# MA-Ethernet.net
KiCad netlist of a schematic drawn in Altium Designer
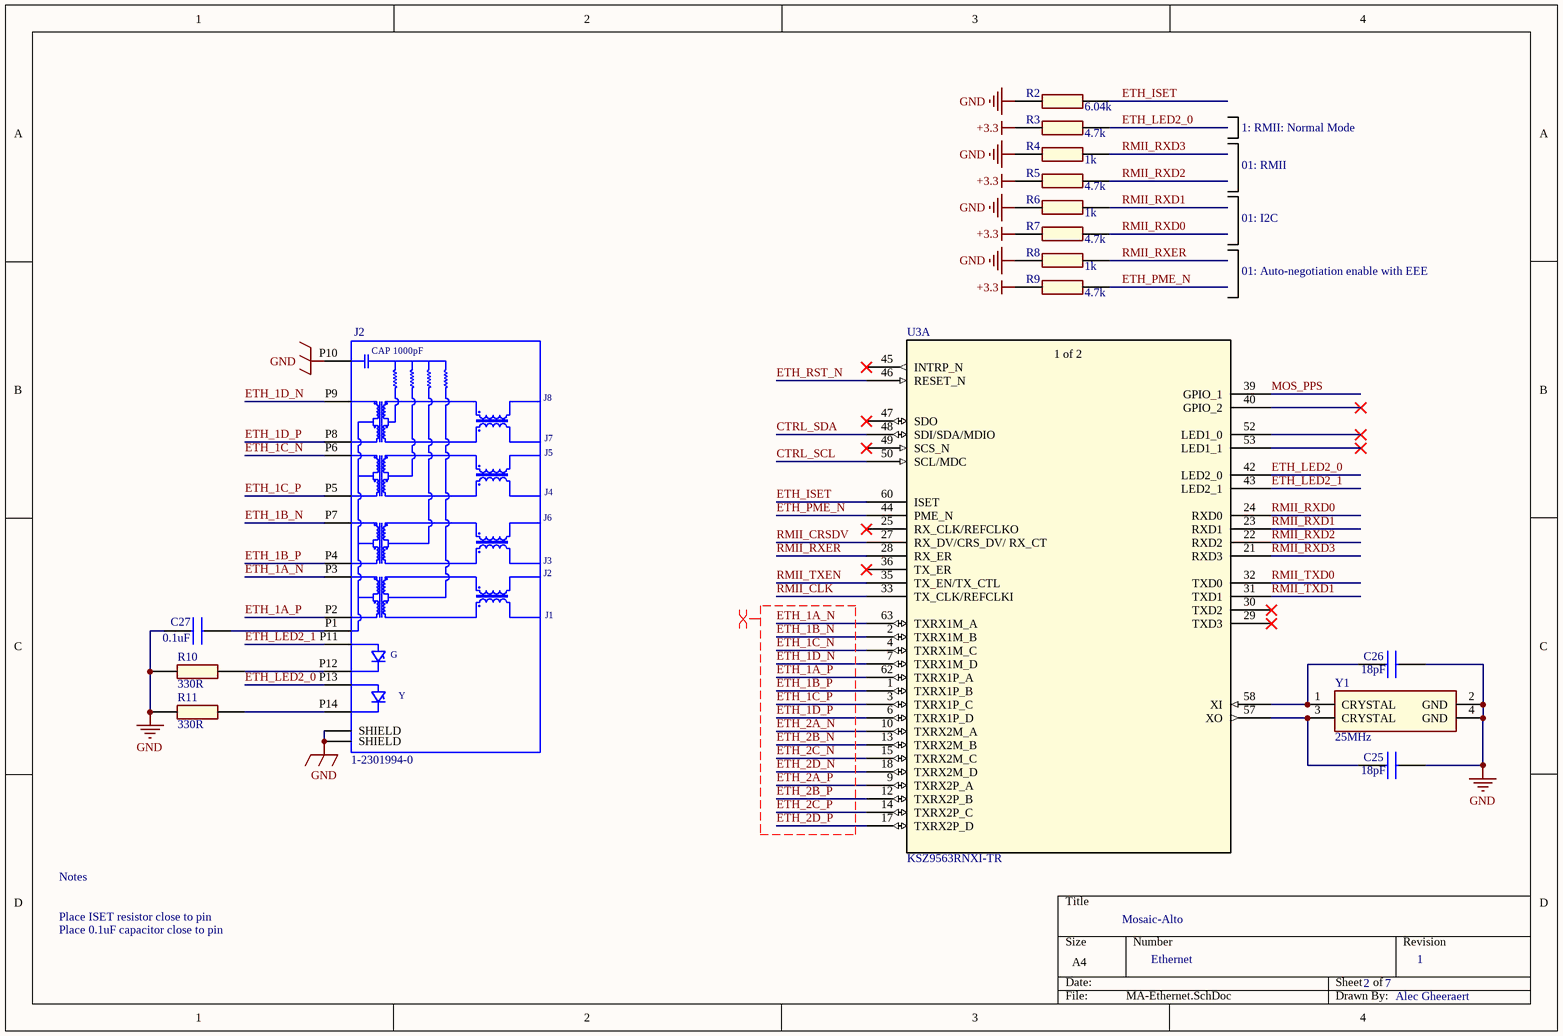
[diagram p0: MA-Ethernet.SchDoc]

(export (version "E")
  (design (tool "Eeschema 10.0.6"))
  (components
    (comp (ref "C25")
      (value "18pF")
      (footprint "CAPC1608X87N")
      (description "0603 18pF")
      (fields (field (name "TOLERANCE") "5%") (field (name "MANUFACTURER") "Walsin"))
      (libsource (lib "Ghrt") (part "0603N180J160CT"))
    )
    (comp (ref "C26")
      (value "18pF")
      (footprint "CAPC1608X87N")
      (description "0603 18pF")
      (fields (field (name "TOLERANCE") "5%") (field (name "MANUFACTURER") "Walsin"))
      (libsource (lib "Ghrt") (part "0603N180J160CT"))
    )
    (comp (ref "C27")
      (value "0.1uF")
      (footprint "CAPC2012X145N")
      (description "0805I 0.1µF")
      (fields (field (name "MANUFACTURER") "Walsin") (field (name "TOLERANCE") "10%"))
      (libsource (lib "Ghrt") (part "MG21B104K101CT"))
    )
    (comp (ref "J2")
      (value "1-2301994-0")
      (footprint "1-2301994-0")
      (description "RJ45 1Gbit MJ")
      (fields (field (name "MANUFACTURER") "TE Connectivity"))
      (libsource (lib "Ghrt") (part "1-2301994-0"))
    )
    (comp (ref "R2")
      (value "6.04k")
      (footprint "RESC1005X40N")
      (description "0402I 6.04k")
      (fields (field (name "MANUFACTURER") "Walsin") (field (name "TOLERANCE") "1%"))
      (libsource (lib "Ghrt") (part "WR04X6041FTL"))
    )
    (comp (ref "R3")
      (value "4.7k")
      (footprint "RESC1005X40N")
      (description "0402I 4.7k")
      (fields (field (name "MANUFACTURER") "Walsin") (field (name "TOLERANCE") "1%"))
      (libsource (lib "Ghrt") (part "WR04X4701FTL"))
    )
    (comp (ref "R4")
      (value "1k")
      (footprint "RESC1005X40N")
      (description "0402I 1k")
      (fields (field (name "MANUFACTURER") "Walsin") (field (name "TOLERANCE") "1%"))
      (libsource (lib "Ghrt") (part "WR04X1001FTL"))
    )
    (comp (ref "R5")
      (value "4.7k")
      (footprint "RESC1005X40N")
      (description "0402I 4.7k")
      (fields (field (name "MANUFACTURER") "Walsin") (field (name "TOLERANCE") "1%"))
      (libsource (lib "Ghrt") (part "WR04X4701FTL"))
    )
    (comp (ref "R6")
      (value "1k")
      (footprint "RESC1005X40N")
      (description "0402I 1k")
      (fields (field (name "MANUFACTURER") "Walsin") (field (name "TOLERANCE") "1%"))
      (libsource (lib "Ghrt") (part "WR04X1001FTL"))
    )
    (comp (ref "R7")
      (value "4.7k")
      (footprint "RESC1005X40N")
      (description "0402I 4.7k")
      (fields (field (name "MANUFACTURER") "Walsin") (field (name "TOLERANCE") "1%"))
      (libsource (lib "Ghrt") (part "WR04X4701FTL"))
    )
    (comp (ref "R8")
      (value "1k")
      (footprint "RESC1005X40N")
      (description "0402I 1k")
      (fields (field (name "MANUFACTURER") "Walsin") (field (name "TOLERANCE") "1%"))
      (libsource (lib "Ghrt") (part "WR04X1001FTL"))
    )
    (comp (ref "R9")
      (value "4.7k")
      (footprint "RESC1005X40N")
      (description "0402I 4.7k")
      (fields (field (name "MANUFACTURER") "Walsin") (field (name "TOLERANCE") "1%"))
      (libsource (lib "Ghrt") (part "WR04X4701FTL"))
    )
    (comp (ref "R10")
      (value "330R")
      (footprint "RESC1005X40N")
      (description "0402I 330")
      (fields (field (name "TOLERANCE") "1%") (field (name "MANUFACTURER") "Walsin"))
      (libsource (lib "Ghrt") (part "WR04X3300FTL"))
    )
    (comp (ref "R11")
      (value "330R")
      (footprint "RESC1005X40N")
      (description "0402I 330")
      (fields (field (name "TOLERANCE") "1%") (field (name "MANUFACTURER") "Walsin"))
      (libsource (lib "Ghrt") (part "WR04X3300FTL"))
    )
    (comp (ref "U3")
      (value "KSZ9563RNXI-TR")
      (footprint "VQFN64_NX_MCH")
      (description "3-Port Gigabit Ethernet Switch")
      (fields (field (name "MANUFACTURER") "Texas Instruments"))
      (libsource (lib "Ghrt") (part "KSZ9563RNXI-TR"))
    )
    (comp (ref "Y1")
      (value "25MHz")
      (footprint "LFXTAL055474REEL")
      (description "25MHz +/-50ppm Crystal")
      (fields (field (name "MANUFACTURER") "IQD") (field (name "TOLERANCE") "50PPM"))
      (libsource (lib "Ghrt") (part "LFXTAL055474REEL"))
    )
  )
  (nets
    (net (code "1") (name "+3.3") (class "Default")
      (node (ref "R3") (pin "1") (pinfunction "1_1") (pintype "passive"))
      (node (ref "R5") (pin "1") (pinfunction "1_1") (pintype "passive"))
      (node (ref "R7") (pin "1") (pinfunction "1_1") (pintype "passive"))
      (node (ref "R9") (pin "1") (pinfunction "1_1") (pintype "passive"))
    )
    (net (code "2") (name "/CTRL_SCL") (class "Default")
      (node (ref "U3") (pin "50") (pinfunction "SCL/MDC_50") (pintype "input"))
    )
    (net (code "3") (name "/CTRL_SDA") (class "Default")
      (node (ref "U3") (pin "48") (pinfunction "SDI/SDA/MDIO_48") (pintype "bidirectional"))
    )
    (net (code "4") (name "/ETH_1A_N") (class "Default")
      (node (ref "J2") (pin "P3") (pinfunction "P3_P3") (pintype "passive"))
      (node (ref "U3") (pin "63") (pinfunction "TXRX1M_A_63") (pintype "bidirectional"))
    )
    (net (code "5") (name "/ETH_1A_P") (class "Default")
      (node (ref "J2") (pin "P2") (pinfunction "P2_P2") (pintype "passive"))
      (node (ref "U3") (pin "62") (pinfunction "TXRX1P_A_62") (pintype "bidirectional"))
    )
    (net (code "6") (name "/ETH_1B_N") (class "Default")
      (node (ref "J2") (pin "P7") (pinfunction "P7_P7") (pintype "passive"))
      (node (ref "U3") (pin "2") (pinfunction "TXRX1M_B_2") (pintype "bidirectional"))
    )
    (net (code "7") (name "/ETH_1B_P") (class "Default")
      (node (ref "J2") (pin "P4") (pinfunction "P4_P4") (pintype "passive"))
      (node (ref "U3") (pin "1") (pinfunction "TXRX1P_B_1") (pintype "bidirectional"))
    )
    (net (code "8") (name "/ETH_1C_N") (class "Default")
      (node (ref "J2") (pin "P6") (pinfunction "P6_P6") (pintype "passive"))
      (node (ref "U3") (pin "4") (pinfunction "TXRX1M_C_4") (pintype "bidirectional"))
    )
    (net (code "9") (name "/ETH_1C_P") (class "Default")
      (node (ref "J2") (pin "P5") (pinfunction "P5_P5") (pintype "passive"))
      (node (ref "U3") (pin "3") (pinfunction "TXRX1P_C_3") (pintype "bidirectional"))
    )
    (net (code "10") (name "/ETH_1D_N") (class "Default")
      (node (ref "J2") (pin "P9") (pinfunction "P9_P9") (pintype "passive"))
      (node (ref "U3") (pin "7") (pinfunction "TXRX1M_D_7") (pintype "bidirectional"))
    )
    (net (code "11") (name "/ETH_1D_P") (class "Default")
      (node (ref "J2") (pin "P8") (pinfunction "P8_P8") (pintype "passive"))
      (node (ref "U3") (pin "6") (pinfunction "TXRX1P_D_6") (pintype "bidirectional"))
    )
    (net (code "12") (name "/ETH_2A_N") (class "Default")
      (node (ref "U3") (pin "10") (pinfunction "TXRX2M_A_10") (pintype "bidirectional"))
    )
    (net (code "13") (name "/ETH_2A_P") (class "Default")
      (node (ref "U3") (pin "9") (pinfunction "TXRX2P_A_9") (pintype "bidirectional"))
    )
    (net (code "14") (name "/ETH_2B_N") (class "Default")
      (node (ref "U3") (pin "13") (pinfunction "TXRX2M_B_13") (pintype "bidirectional"))
    )
    (net (code "15") (name "/ETH_2B_P") (class "Default")
      (node (ref "U3") (pin "12") (pinfunction "TXRX2P_B_12") (pintype "bidirectional"))
    )
    (net (code "16") (name "/ETH_2C_N") (class "Default")
      (node (ref "U3") (pin "15") (pinfunction "TXRX2M_C_15") (pintype "bidirectional"))
    )
    (net (code "17") (name "/ETH_2C_P") (class "Default")
      (node (ref "U3") (pin "14") (pinfunction "TXRX2P_C_14") (pintype "bidirectional"))
    )
    (net (code "18") (name "/ETH_2D_N") (class "Default")
      (node (ref "U3") (pin "18") (pinfunction "TXRX2M_D_18") (pintype "bidirectional"))
    )
    (net (code "19") (name "/ETH_2D_P") (class "Default")
      (node (ref "U3") (pin "17") (pinfunction "TXRX2P_D_17") (pintype "bidirectional"))
    )
    (net (code "20") (name "/ETH_ISET") (class "Default")
      (node (ref "R2") (pin "2") (pinfunction "2_2") (pintype "passive"))
      (node (ref "U3") (pin "60") (pinfunction "ISET_60") (pintype "passive"))
    )
    (net (code "21") (name "/ETH_LED2_0") (class "Default")
      (node (ref "J2") (pin "P13") (pinfunction "P13_P13") (pintype "passive"))
      (node (ref "R3") (pin "2") (pinfunction "2_2") (pintype "passive"))
      (node (ref "U3") (pin "42") (pinfunction "LED2_0_42") (pintype "passive"))
    )
    (net (code "22") (name "/ETH_LED2_1") (class "Default")
      (node (ref "J2") (pin "P11") (pinfunction "P11_P11") (pintype "passive"))
      (node (ref "U3") (pin "43") (pinfunction "LED2_1_43") (pintype "passive"))
    )
    (net (code "23") (name "/ETH_PME_N") (class "Default")
      (node (ref "R9") (pin "2") (pinfunction "2_2") (pintype "passive"))
      (node (ref "U3") (pin "44") (pinfunction "PME_N_44") (pintype "passive"))
    )
    (net (code "24") (name "/ETH_RST_N") (class "Default")
      (node (ref "U3") (pin "46") (pinfunction "RESET_N_46") (pintype "input"))
    )
    (net (code "25") (name "/MOS_PPS") (class "Default")
      (node (ref "U3") (pin "39") (pinfunction "GPIO_1_39") (pintype "passive"))
    )
    (net (code "26") (name "/RMII_CLK") (class "Default")
      (node (ref "U3") (pin "33") (pinfunction "TX_CLK/REFCLKI_33") (pintype "passive"))
    )
    (net (code "27") (name "/RMII_CRSDV") (class "Default")
      (node (ref "U3") (pin "27") (pinfunction "RX_DV/CRS_DV/_RX_CT_27") (pintype "passive"))
    )
    (net (code "28") (name "/RMII_RXD0") (class "Default")
      (node (ref "R7") (pin "2") (pinfunction "2_2") (pintype "passive"))
      (node (ref "U3") (pin "24") (pinfunction "RXD0_24") (pintype "passive"))
    )
    (net (code "29") (name "/RMII_RXD1") (class "Default")
      (node (ref "R6") (pin "2") (pinfunction "2_2") (pintype "passive"))
      (node (ref "U3") (pin "23") (pinfunction "RXD1_23") (pintype "passive"))
    )
    (net (code "30") (name "/RMII_RXD2") (class "Default")
      (node (ref "R5") (pin "2") (pinfunction "2_2") (pintype "passive"))
      (node (ref "U3") (pin "22") (pinfunction "RXD2_22") (pintype "passive"))
    )
    (net (code "31") (name "/RMII_RXD3") (class "Default")
      (node (ref "R4") (pin "2") (pinfunction "2_2") (pintype "passive"))
      (node (ref "U3") (pin "21") (pinfunction "RXD3_21") (pintype "passive"))
    )
    (net (code "32") (name "/RMII_RXER") (class "Default")
      (node (ref "R8") (pin "2") (pinfunction "2_2") (pintype "passive"))
      (node (ref "U3") (pin "28") (pinfunction "RX_ER_28") (pintype "passive"))
    )
    (net (code "33") (name "/RMII_TXD0") (class "Default")
      (node (ref "U3") (pin "32") (pinfunction "TXD0_32") (pintype "passive"))
    )
    (net (code "34") (name "/RMII_TXD1") (class "Default")
      (node (ref "U3") (pin "31") (pinfunction "TXD1_31") (pintype "passive"))
    )
    (net (code "35") (name "/RMII_TXEN") (class "Default")
      (node (ref "U3") (pin "35") (pinfunction "TX_EN/TX_CTL_35") (pintype "passive"))
    )
    (net (code "36") (name "GND") (class "Default")
      (node (ref "C25") (pin "2") (pinfunction "2_2") (pintype "passive"))
      (node (ref "C26") (pin "2") (pinfunction "2_2") (pintype "passive"))
      (node (ref "C27") (pin "2") (pinfunction "2_2") (pintype "passive"))
      (node (ref "J2") (pin "P10") (pinfunction "P10_P10") (pintype "passive"))
      (node (ref "J2") (pin "S1") (pinfunction "SHIELD_S1") (pintype "power_in"))
      (node (ref "J2") (pin "S2") (pinfunction "SHIELD_S2") (pintype "power_in"))
      (node (ref "R10") (pin "2") (pinfunction "2_2") (pintype "passive"))
      (node (ref "R11") (pin "2") (pinfunction "2_2") (pintype "passive"))
      (node (ref "R2") (pin "1") (pinfunction "1_1") (pintype "passive"))
      (node (ref "R4") (pin "1") (pinfunction "1_1") (pintype "passive"))
      (node (ref "R6") (pin "1") (pinfunction "1_1") (pintype "passive"))
      (node (ref "R8") (pin "1") (pinfunction "1_1") (pintype "passive"))
      (node (ref "Y1") (pin "2") (pinfunction "GND_2") (pintype "passive"))
      (node (ref "Y1") (pin "4") (pinfunction "GND_4") (pintype "passive"))
    )
    (net (code "37") (name "Net-(C27-Pad1)") (class "Default")
      (node (ref "C27") (pin "1") (pinfunction "1_1") (pintype "passive"))
      (node (ref "J2") (pin "P1") (pinfunction "P1_P1") (pintype "passive"))
    )
    (net (code "38") (name "Net-(J2-PadP12)") (class "Default")
      (node (ref "J2") (pin "P12") (pinfunction "P12_P12") (pintype "passive"))
      (node (ref "R10") (pin "1") (pinfunction "1_1") (pintype "passive"))
    )
    (net (code "39") (name "Net-(J2-PadP14)") (class "Default")
      (node (ref "J2") (pin "P14") (pinfunction "P14_P14") (pintype "passive"))
      (node (ref "R11") (pin "1") (pinfunction "1_1") (pintype "passive"))
    )
    (net (code "40") (name "Net-(U3A-XI)") (class "Default")
      (node (ref "C26") (pin "1") (pinfunction "1_1") (pintype "passive"))
      (node (ref "U3") (pin "58") (pinfunction "XI_58") (pintype "input"))
      (node (ref "Y1") (pin "1") (pinfunction "CRYSTAL_1") (pintype "passive"))
    )
    (net (code "41") (name "Net-(U3A-XO)") (class "Default")
      (node (ref "C25") (pin "1") (pinfunction "1_1") (pintype "passive"))
      (node (ref "U3") (pin "57") (pinfunction "XO_57") (pintype "output"))
      (node (ref "Y1") (pin "3") (pinfunction "CRYSTAL_3") (pintype "passive"))
    )
    (net (code "42") (name "unconnected-(U3A-GPIO_2-Pad40)") (class "Default")
      (node (ref "U3") (pin "40") (pinfunction "GPIO_2_40") (pintype "passive+no_connect"))
    )
    (net (code "43") (name "unconnected-(U3A-INTRP_N-Pad45)") (class "Default")
      (node (ref "U3") (pin "45") (pinfunction "INTRP_N_45") (pintype "output+no_connect"))
    )
    (net (code "44") (name "unconnected-(U3A-LED1_0-Pad52)") (class "Default")
      (node (ref "U3") (pin "52") (pinfunction "LED1_0_52") (pintype "passive+no_connect"))
    )
    (net (code "45") (name "unconnected-(U3A-LED1_1-Pad53)") (class "Default")
      (node (ref "U3") (pin "53") (pinfunction "LED1_1_53") (pintype "passive+no_connect"))
    )
    (net (code "46") (name "unconnected-(U3A-RX_CLK{slash}REFCLKO-Pad25)") (class "Default")
      (node (ref "U3") (pin "25") (pinfunction "RX_CLK/REFCLKO_25") (pintype "passive+no_connect"))
    )
    (net (code "47") (name "unconnected-(U3A-SCS_N-Pad49)") (class "Default")
      (node (ref "U3") (pin "49") (pinfunction "SCS_N_49") (pintype "input+no_connect"))
    )
    (net (code "48") (name "unconnected-(U3A-SDO-Pad47)") (class "Default")
      (node (ref "U3") (pin "47") (pinfunction "SDO_47") (pintype "bidirectional+no_connect"))
    )
    (net (code "49") (name "unconnected-(U3A-TXD2-Pad30)") (class "Default")
      (node (ref "U3") (pin "30") (pinfunction "TXD2_30") (pintype "passive+no_connect"))
    )
    (net (code "50") (name "unconnected-(U3A-TXD3-Pad29)") (class "Default")
      (node (ref "U3") (pin "29") (pinfunction "TXD3_29") (pintype "passive+no_connect"))
    )
    (net (code "51") (name "unconnected-(U3A-TX_ER-Pad36)") (class "Default")
      (node (ref "U3") (pin "36") (pinfunction "TX_ER_36") (pintype "passive+no_connect"))
    )
  )
)
